# SCH_Personal-Card-V2_2024-07-08.net
KiCad netlist of a schematic drawn in EasyEDA
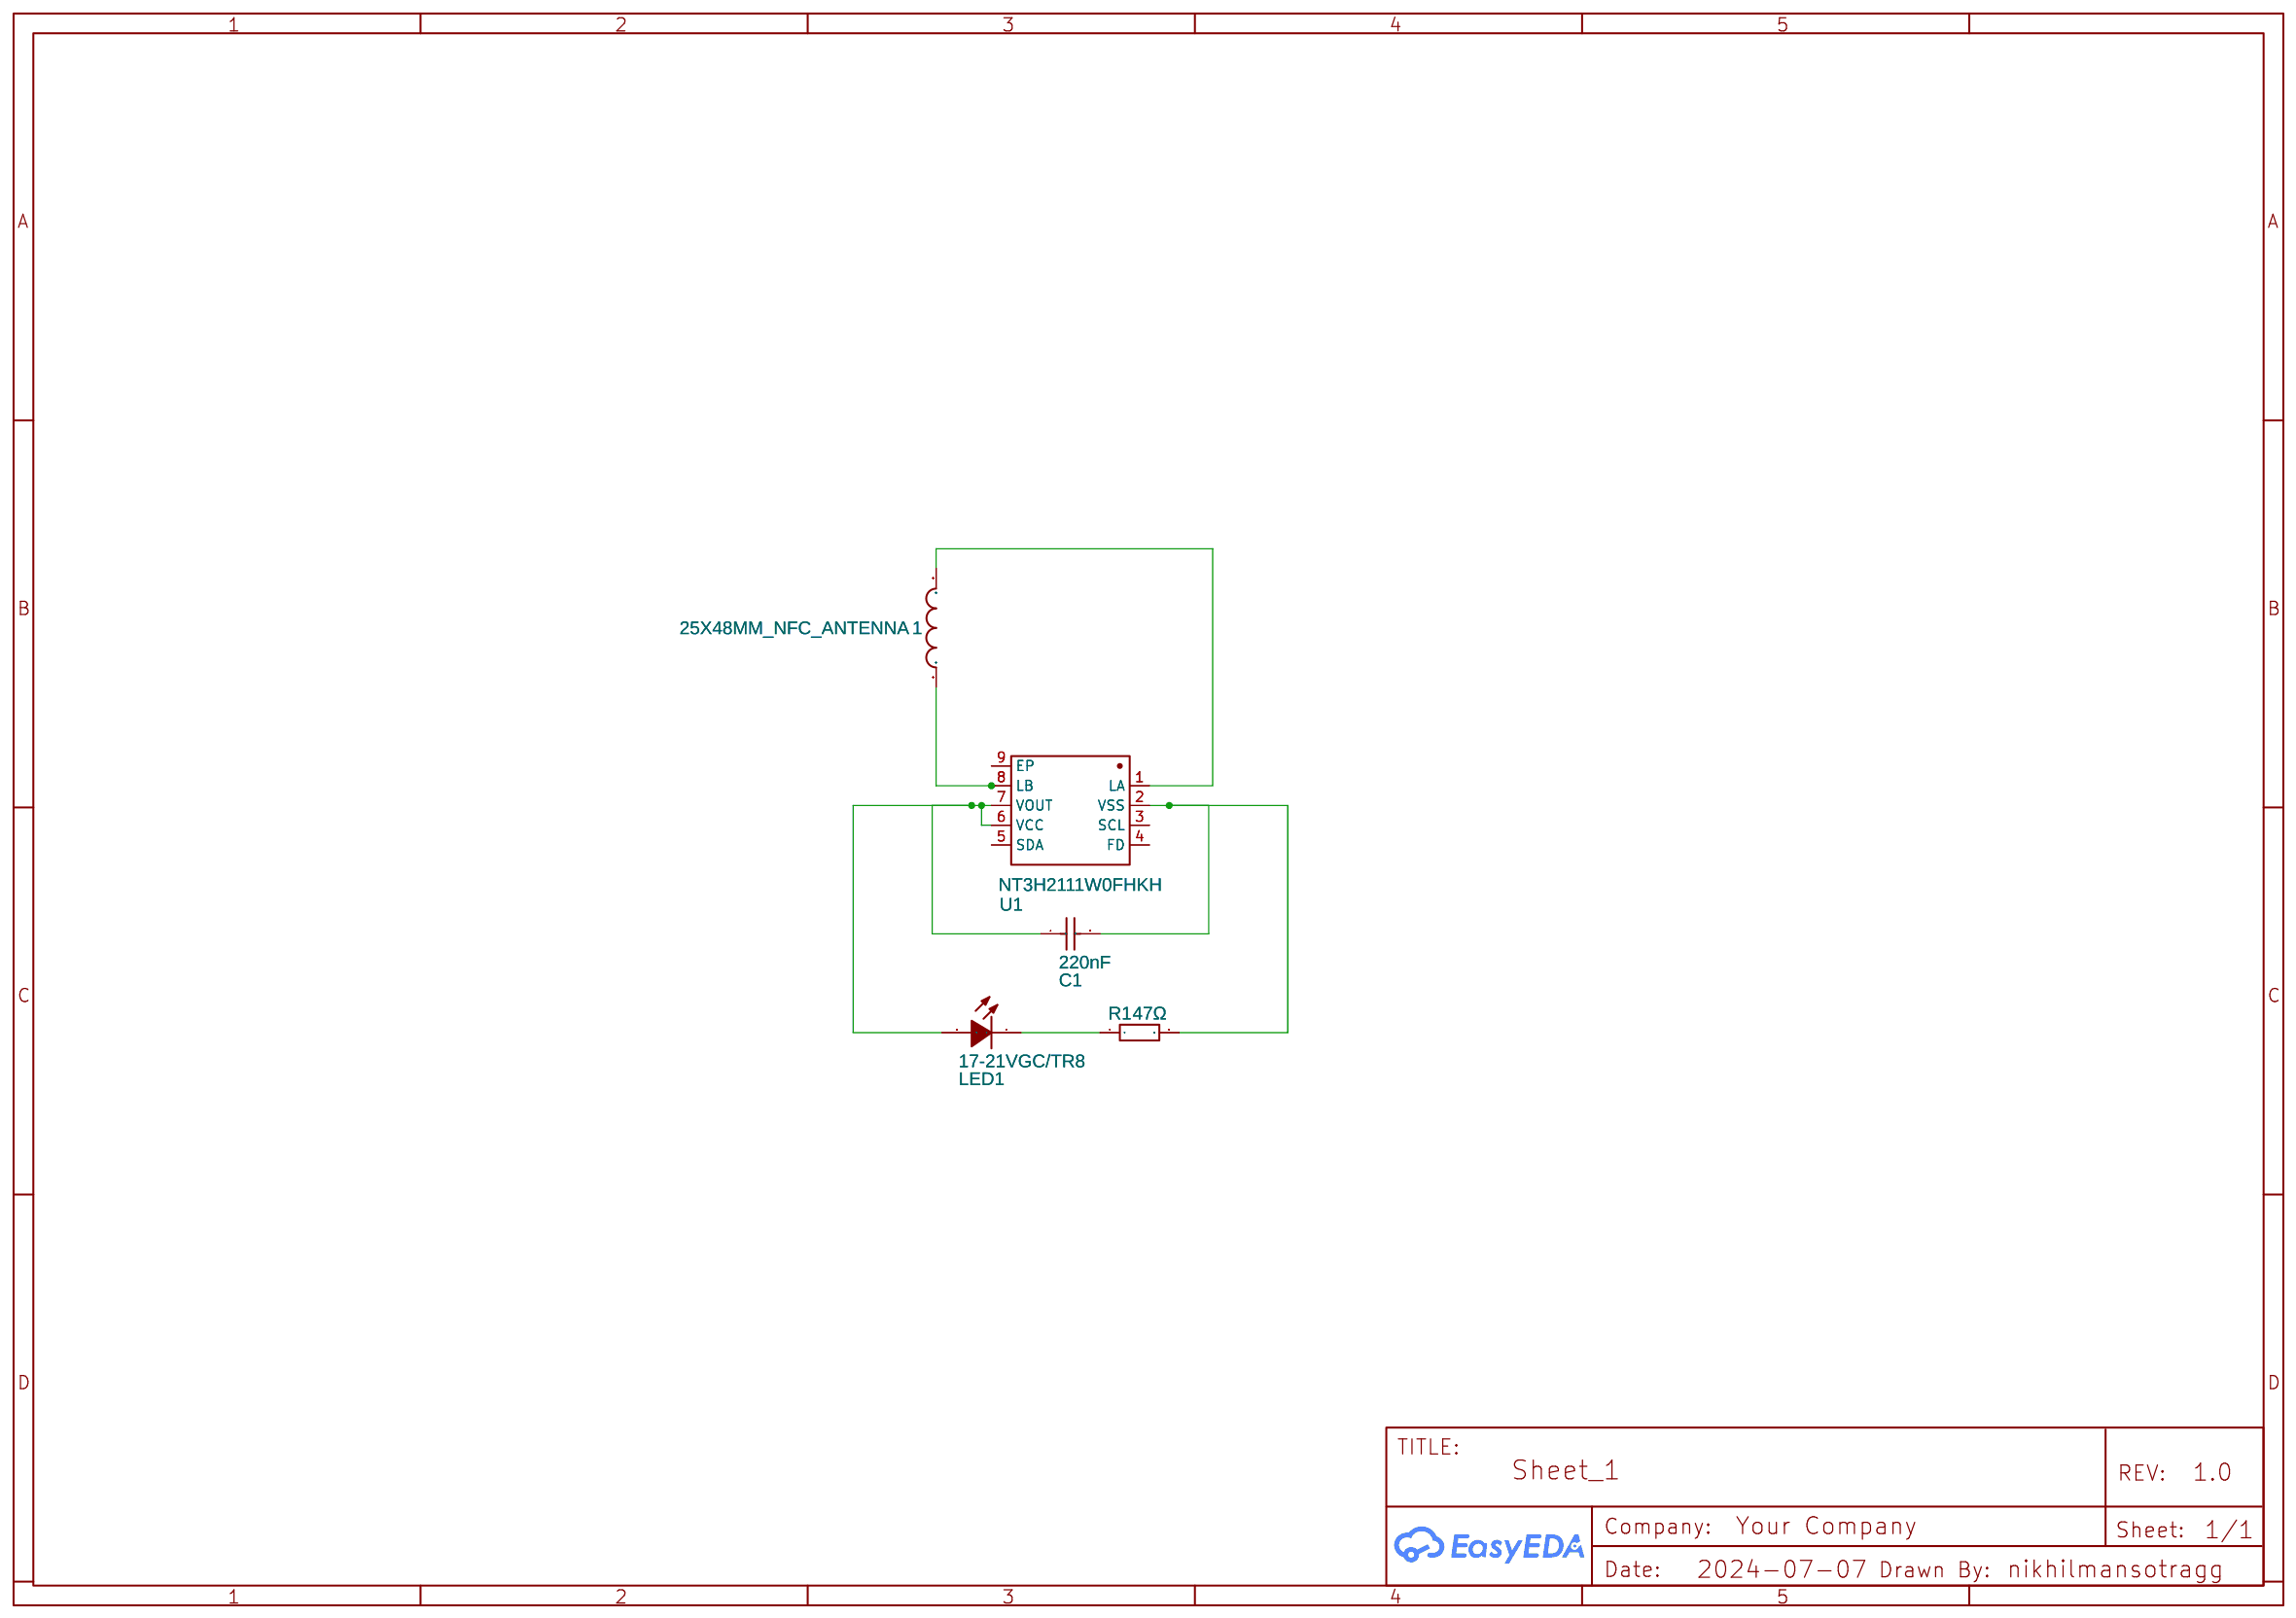
[diagram p0: schematic sheet]

(export (version "E")
  (design (tool "Eeschema 10.0.6"))
  (components
    (comp (ref "1") (value "25X48MM_NFC_ANTENNA") (libsource (lib "") (part "25X48MM_NFC_ANTENNA")))
    (comp (ref "C1")
      (value "220nF")
      (fields
        (field (name "Manufacturer Part") "CL10B224KA8NNNC")
        (field (name "Manufacturer") "SAMSUNG(三星)")
      )
      (libsource (lib "") (part "CL10B224KA8NNNC"))
    )
    (comp (ref "LED1")
      (value "17-21VGC/TR8")
      (fields (field (name "Manufacturer") "EVERLIGHT(亿光)"))
      (libsource (lib "") (part "17-21VGC/TR8"))
    )
    (comp (ref "R1")
      (value "47Ω")
      (fields
        (field (name "Manufacturer Part") "0603WAF470JT5E")
        (field (name "Manufacturer") "UNI-ROYAL(厚声)")
      )
      (libsource (lib "") (part "0603WAF470JT5E"))
    )
    (comp (ref "U1")
      (value "NT3H2111W0FHKH")
      (fields (field (name "Manufacturer") "NXP(恩智浦)"))
      (libsource (lib "") (part "NT3H2111W0FHKH"))
    )
  )
  (nets
    (net (code "1") (name "Net-(LED1-+)") (class "Default")
      (node (ref "C1") (pin "1") (pinfunction "1_1") (pintype "input"))
      (node (ref "LED1") (pin "2") (pinfunction "+_2") (pintype "unspecified"))
      (node (ref "U1") (pin "6") (pinfunction "VCC_6") (pintype "unspecified"))
      (node (ref "U1") (pin "7") (pinfunction "VOUT_7") (pintype "unspecified"))
    )
    (net (code "2") (name "Net-(LED1--)") (class "Default")
      (node (ref "LED1") (pin "1") (pinfunction "-_1") (pintype "unspecified"))
      (node (ref "R1") (pin "1") (pinfunction "1_1") (pintype "input"))
    )
    (net (code "3") (name "Net-(U1-LA)") (class "Default")
      (node (ref "1") (pin "P$2") (pinfunction "P$2_P$2") (pintype "bidirectional"))
      (node (ref "U1") (pin "1") (pinfunction "LA_1") (pintype "unspecified"))
    )
    (net (code "4") (name "Net-(U1-LB)") (class "Default")
      (node (ref "1") (pin "P$1") (pinfunction "P$1_P$1") (pintype "bidirectional"))
      (node (ref "U1") (pin "8") (pinfunction "LB_8") (pintype "unspecified"))
    )
    (net (code "5") (name "Net-(U1-VSS)") (class "Default")
      (node (ref "C1") (pin "2") (pinfunction "2_2") (pintype "input"))
      (node (ref "R1") (pin "2") (pinfunction "2_2") (pintype "input"))
      (node (ref "U1") (pin "2") (pinfunction "VSS_2") (pintype "unspecified"))
    )
    (net (code "6") (name "unconnected-(U1-EP-Pad9)") (class "Default")
      (node (ref "U1") (pin "9") (pinfunction "EP_9") (pintype "unspecified"))
    )
    (net (code "7") (name "unconnected-(U1-FD-Pad4)") (class "Default")
      (node (ref "U1") (pin "4") (pinfunction "FD_4") (pintype "unspecified"))
    )
    (net (code "8") (name "unconnected-(U1-SCL-Pad3)") (class "Default")
      (node (ref "U1") (pin "3") (pinfunction "SCL_3") (pintype "unspecified"))
    )
    (net (code "9") (name "unconnected-(U1-SDA-Pad5)") (class "Default")
      (node (ref "U1") (pin "5") (pinfunction "SDA_5") (pintype "unspecified"))
    )
  )
)
